# Sheet3.net
KiCad netlist of a schematic drawn in Altium Designer
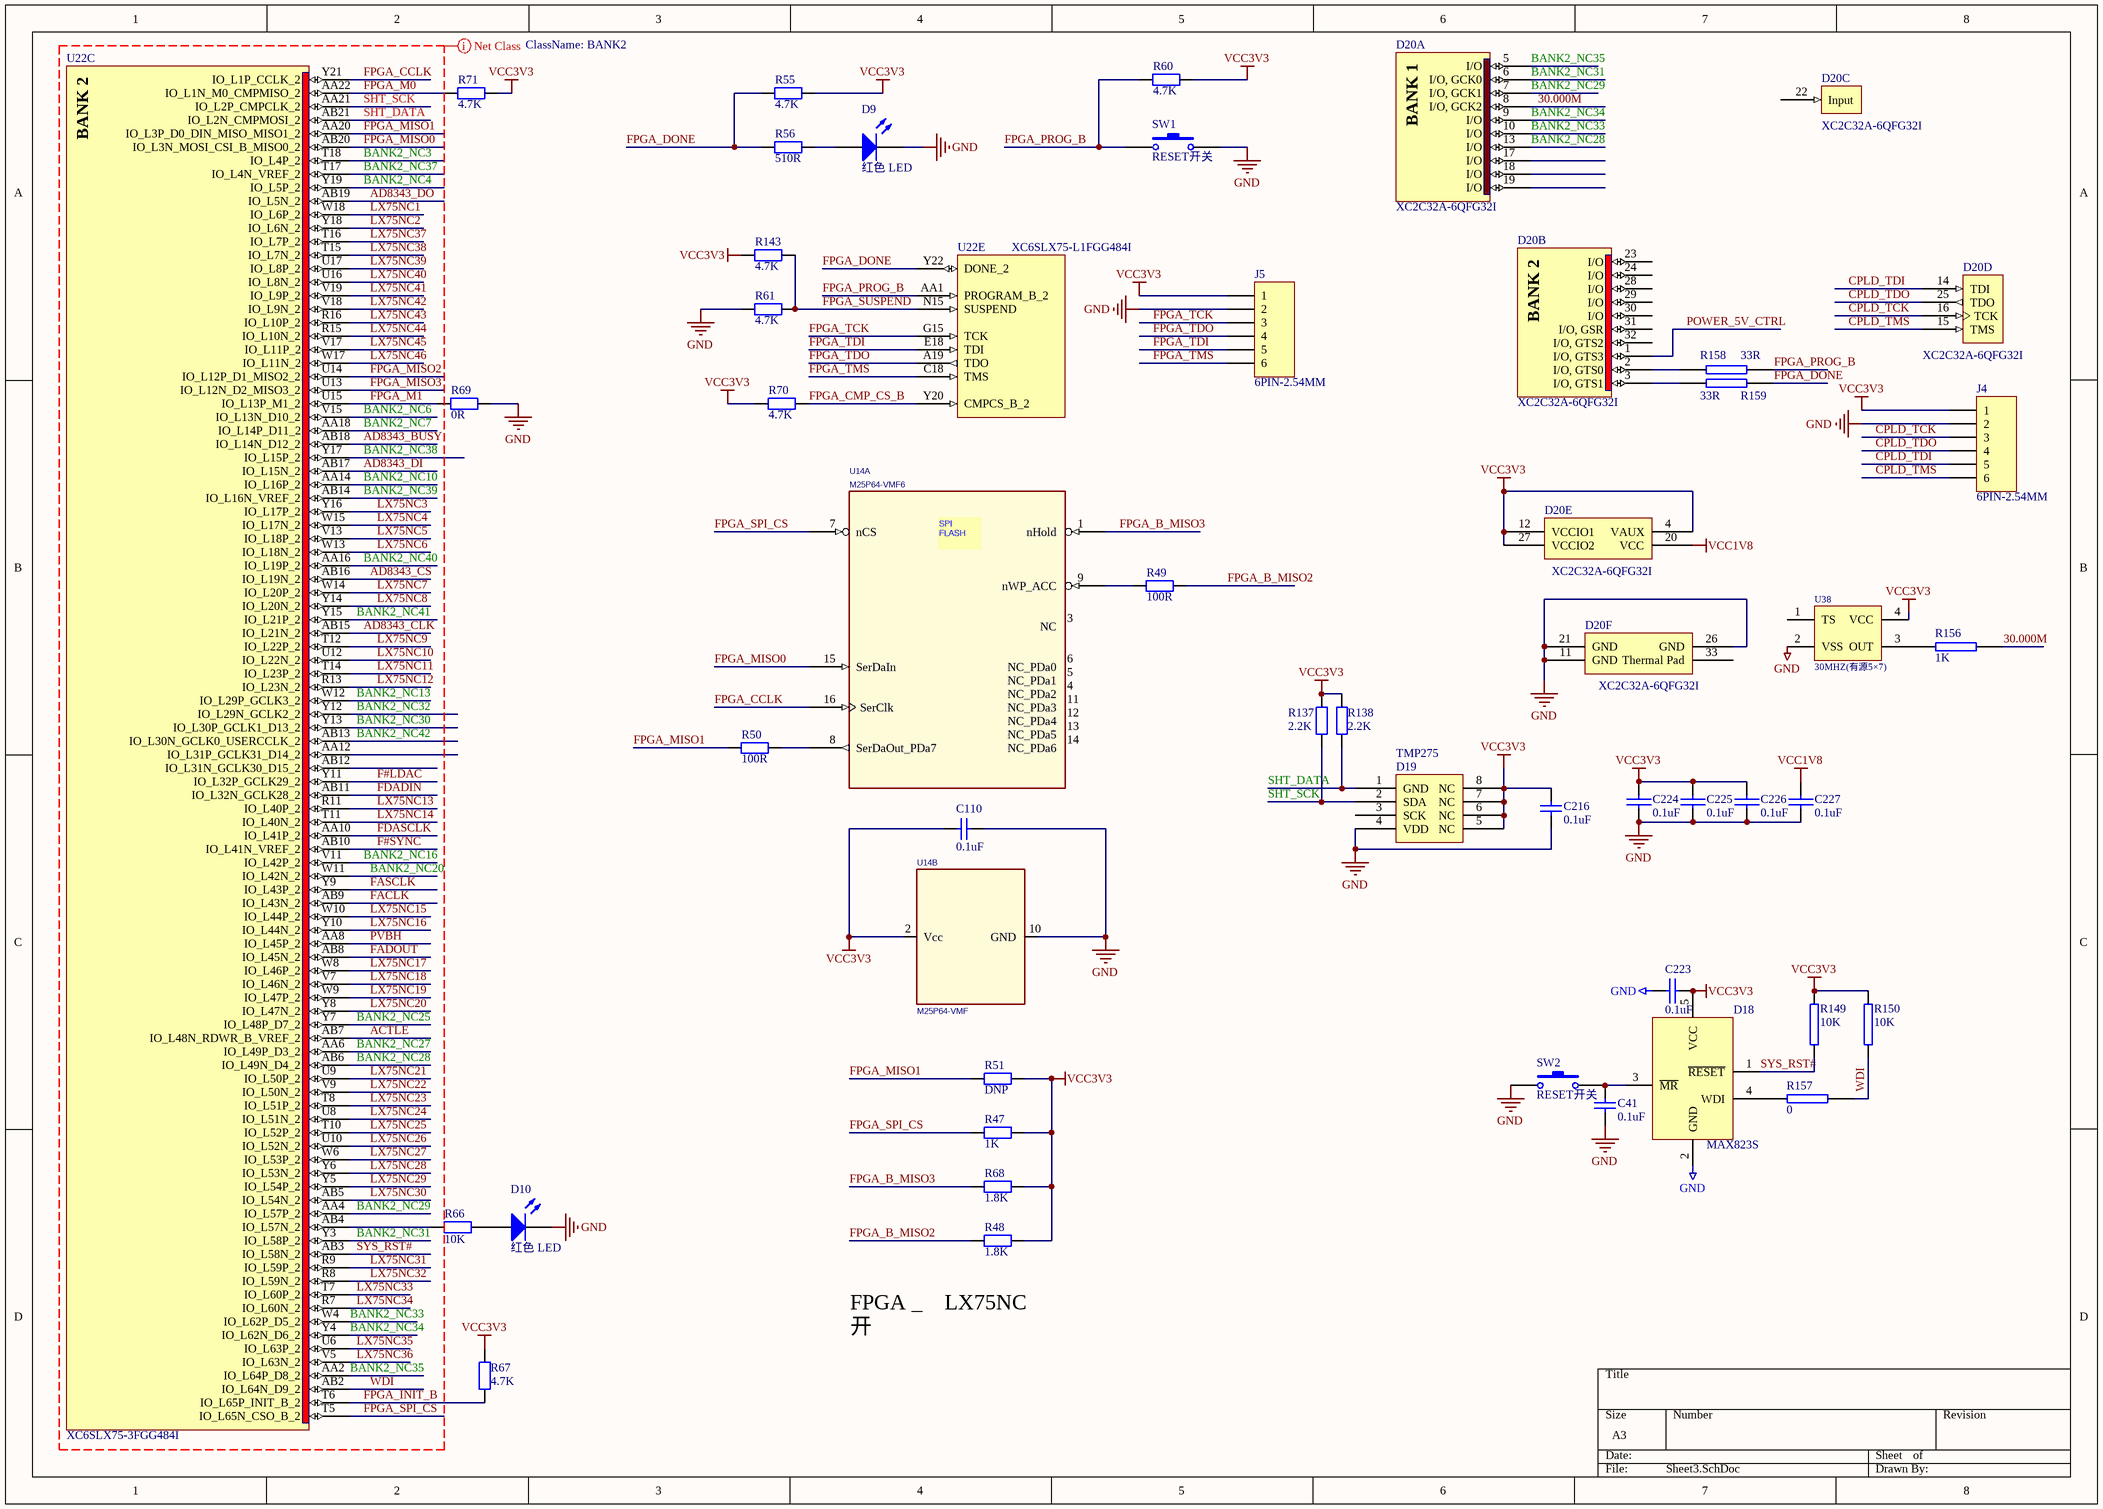
[diagram p0: Sheet3.SchDoc]

(export (version "E")
  (design (tool "Eeschema 10.0.6"))
  (components
    (comp (ref "C41")
      (value "0.1uF")
      (footprint "0603C")
      (description "Capacitor")
      (fields (field (name "PUBLISHER") "Altium Limited"))
      (libsource (lib "Miscellaneous Devices") (part "Cap"))
    )
    (comp (ref "C110")
      (value "0.1uF")
      (footprint "0402C")
      (description "Capacitor")
      (fields (field (name "PUBLISHER") "Altium Limited"))
      (libsource (lib "Miscellaneous Devices") (part "Cap"))
    )
    (comp (ref "C216")
      (value "0.1uF")
      (footprint "0402C")
      (description "Capacitor")
      (fields (field (name "PUBLISHER") "Altium Limited"))
      (libsource (lib "Miscellaneous Devices") (part "Cap"))
    )
    (comp (ref "C223") (value "0.1uF") (footprint "0603X") (libsource (lib "*") (part "2543.S01_104_49")))
    (comp (ref "C224") (value "0.1uF") (footprint "0402C") (libsource (lib "*") (part "2543.S01_104_49")))
    (comp (ref "C225") (value "0.1uF") (footprint "0402C") (libsource (lib "*") (part "2543.S01_104_49")))
    (comp (ref "C226") (value "0.1uF") (footprint "0402C") (libsource (lib "*") (part "2543.S01_104_49")))
    (comp (ref "C227") (value "0.1uF") (footprint "0402C") (libsource (lib "*") (part "2543.S01_104_49")))
    (comp (ref "D9")
      (value "红色 LED")
      (footprint "0805LED")
      (description "Typical RED, GREEN, YELLOW, AMBER GaAs LED")
      (fields (field (name "PUBLISHER") "Altium Limited"))
      (libsource (lib "Miscellaneous Devices") (part "LED2"))
    )
    (comp (ref "D10")
      (value "红色 LED")
      (footprint "0805LED")
      (description "Typical INFRARED GaAs LED")
      (fields (field (name "PUBLISHER") "Altium Limited"))
      (libsource (lib "Miscellaneous Devices") (part "LED0"))
    )
    (comp (ref "D18")
      (value "MAX823S")
      (footprint "MAX823")
      (description "MAX823复位监控芯片")
      (libsource (lib "*") (part "MAX823"))
    )
    (comp (ref "D19") (value "TMP275") (footprint "SMD8XX") (libsource (lib "Schlib1") (part "SHT11")))
    (comp (ref "D20")
      (value "XC2C32A-6QFG32I")
      (footprint "QFG32_N")
      (description "CoolRunner-II 1.8V, 32 Macrocell CPLD, 21 User I/Os, 32-Pin QFNL, Commercial Grade, Pb-Free")
      (fields (field (name "PUBLISHER") "Altium Limited"))
      (libsource (lib "Xilinx CoolRunner II") (part "XC2C32A-6QFG32C"))
    )
    (comp (ref "J4")
      (value "6PIN-2.54MM")
      (footprint "SIP6X")
      (description "Header, 6-Pin")
      (fields (field (name "PUBLISHER") "Altium Limited"))
      (libsource (lib "Miscellaneous Connectors") (part "Header 6"))
    )
    (comp (ref "J5")
      (value "6PIN-2.54MM")
      (footprint "SIP6X")
      (description "Header, 6-Pin")
      (fields (field (name "PUBLISHER") "Altium Limited"))
      (libsource (lib "Miscellaneous Connectors") (part "Header 6"))
    )
    (comp (ref "R47")
      (value "1K")
      (footprint "0603R")
      (description "Resistor")
      (fields (field (name "PUBLISHER") "Altium Limited"))
      (libsource (lib "Miscellaneous Devices") (part "Res2"))
    )
    (comp (ref "R48")
      (value "1.8K")
      (footprint "0603R")
      (description "Resistor")
      (fields (field (name "PUBLISHER") "Altium Limited"))
      (libsource (lib "Miscellaneous Devices") (part "Res2"))
    )
    (comp (ref "R49")
      (value "100R")
      (footprint "0603R")
      (description "Resistor")
      (fields (field (name "PUBLISHER") "Altium Limited"))
      (libsource (lib "Miscellaneous Devices") (part "Res2"))
    )
    (comp (ref "R50")
      (value "100R")
      (footprint "0603R")
      (description "Resistor")
      (fields (field (name "PUBLISHER") "Altium Limited"))
      (libsource (lib "Miscellaneous Devices") (part "Res2"))
    )
    (comp (ref "R51")
      (value "DNP")
      (footprint "0603R")
      (description "Resistor")
      (fields (field (name "PUBLISHER") "Altium Limited"))
      (libsource (lib "Miscellaneous Devices") (part "Res2"))
    )
    (comp (ref "R55")
      (value "4.7K")
      (footprint "0603R")
      (description "Resistor")
      (fields (field (name "PUBLISHER") "Altium Limited"))
      (libsource (lib "Miscellaneous Devices") (part "Res2"))
    )
    (comp (ref "R56")
      (value "510R")
      (footprint "0603R")
      (description "Resistor")
      (fields (field (name "PUBLISHER") "Altium Limited"))
      (libsource (lib "Miscellaneous Devices") (part "Res2"))
    )
    (comp (ref "R60")
      (value "4.7K")
      (footprint "0603R")
      (description "Resistor")
      (fields (field (name "PUBLISHER") "Altium Limited"))
      (libsource (lib "Miscellaneous Devices") (part "Res2"))
    )
    (comp (ref "R61")
      (value "4.7K")
      (footprint "0603R")
      (description "Resistor")
      (fields (field (name "PUBLISHER") "Altium Limited"))
      (libsource (lib "Miscellaneous Devices") (part "Res2"))
    )
    (comp (ref "R66")
      (value "10K")
      (footprint "0603R")
      (description "Resistor")
      (fields (field (name "PUBLISHER") "Altium Limited"))
      (libsource (lib "Miscellaneous Devices") (part "Res2"))
    )
    (comp (ref "R67")
      (value "4.7K")
      (footprint "0603R")
      (description "Resistor")
      (fields (field (name "PUBLISHER") "Altium Limited"))
      (libsource (lib "") (part "Res2_2"))
    )
    (comp (ref "R68")
      (value "1.8K")
      (footprint "0603R")
      (description "Resistor")
      (fields (field (name "PUBLISHER") "Altium Limited"))
      (libsource (lib "Miscellaneous Devices") (part "Res2"))
    )
    (comp (ref "R69")
      (value "0R")
      (footprint "0603R")
      (description "Resistor")
      (fields (field (name "PUBLISHER") "Altium Limited"))
      (libsource (lib "") (part "Res2_1"))
    )
    (comp (ref "R70")
      (value "4.7K")
      (footprint "0603R")
      (description "Resistor")
      (fields (field (name "PUBLISHER") "Altium Limited"))
      (libsource (lib "Miscellaneous Devices") (part "Res2"))
    )
    (comp (ref "R71")
      (value "4.7K")
      (footprint "0603R")
      (description "Resistor")
      (fields (field (name "PUBLISHER") "Altium Limited"))
      (libsource (lib "") (part "Res2_1"))
    )
    (comp (ref "R137")
      (value "2.2K")
      (footprint "0603R")
      (description "Resistor")
      (fields (field (name "PUBLISHER") "Altium Limited"))
      (libsource (lib "") (part "Res2_1"))
    )
    (comp (ref "R138")
      (value "2.2K")
      (footprint "0603R")
      (description "Resistor")
      (fields (field (name "PUBLISHER") "Altium Limited"))
      (libsource (lib "") (part "Res2_1"))
    )
    (comp (ref "R143")
      (value "4.7K")
      (footprint "0603R")
      (description "Resistor")
      (fields (field (name "PUBLISHER") "Altium Limited"))
      (libsource (lib "Miscellaneous Devices") (part "Res2"))
    )
    (comp (ref "R149")
      (value "10K")
      (footprint "0603X")
      (description "电阻")
      (libsource (lib "") (part "RES2_1"))
    )
    (comp (ref "R150")
      (value "10K")
      (footprint "0603X")
      (description "电阻")
      (libsource (lib "") (part "RES2_1"))
    )
    (comp (ref "R156") (value "1K") (footprint "0603") (libsource (lib "*") (part "RES2")))
    (comp (ref "R157") (value "0") (footprint "0603") (libsource (lib "*") (part "RES2")))
    (comp (ref "R158") (value "33R") (footprint "0603R") (libsource (lib "*") (part "RES2")))
    (comp (ref "R159") (value "33R") (footprint "0603R") (libsource (lib "*") (part "RES2")))
    (comp (ref "SW1")
      (value "RESET开关")
      (footprint "RESETKEY")
      (description "Switch")
      (fields (field (name "PUBLISHER") "Altium Limited"))
      (libsource (lib "Miscellaneous Devices") (part "SW-PB"))
    )
    (comp (ref "SW2")
      (value "RESET开关")
      (footprint "RESETKEY")
      (description "Switch")
      (fields (field (name "PUBLISHER") "Altium Limited"))
      (libsource (lib "Miscellaneous Devices") (part "SW-PB"))
    )
    (comp (ref "U14")
      (value "M25P64-VMF")
      (footprint "SOIC16")
      (description "SPI FLASH 128Mbit, 104MHz, 64kB sector")
      (fields (field (name "FULL PART NO") "S25FL128P0XMFI00") (field (name "MANUFACTURER") "Spansion"))
      (libsource (lib "Mpd_Fpga_1") (part "SPI FLASH 128Mb S25FL128P"))
    )
    (comp (ref "U22")
      (value "XC6SLX75-3FGG484I")
      (footprint "FGG484")
      (fields (field (name "PUBLISHER") "Altium Limited"))
      (libsource (lib "Xilinx Spartan-6") (part "XC6SLX45-L1FGG484I"))
    )
    (comp (ref "U38") (value "30MHZ(有源5×7)") (footprint "30M") (libsource (lib "*") (part "CRYSTAL")))
  )
  (nets
    (net (code "1") (name "/30.000M") (class "Default")
      (node (ref "D20") (pin "8") (pinfunction "I/O,_GCK2_8") (pintype "bidirectional"))
      (node (ref "R156") (pin "2") (pinfunction "2_2") (pintype "passive"))
    )
    (net (code "2") (name "/ACTLE") (class "Default")
      (node (ref "U22") (pin "AB7") (pinfunction "IO_L48N_RDWR_B_VREF_2_AB7") (pintype "bidirectional"))
    )
    (net (code "3") (name "/AD8343_BUSY") (class "Default")
      (node (ref "U22") (pin "AB18") (pinfunction "IO_L14N_D12_2_AB18") (pintype "bidirectional"))
    )
    (net (code "4") (name "/AD8343_CLK") (class "Default")
      (node (ref "U22") (pin "AB15") (pinfunction "IO_L21N_2_AB15") (pintype "bidirectional"))
    )
    (net (code "5") (name "/AD8343_CS") (class "Default")
      (node (ref "U22") (pin "AB16") (pinfunction "IO_L19N_2_AB16") (pintype "bidirectional"))
    )
    (net (code "6") (name "/AD8343_DI") (class "Default")
      (node (ref "U22") (pin "AB17") (pinfunction "IO_L15N_2_AB17") (pintype "bidirectional"))
    )
    (net (code "7") (name "/AD8343_DO") (class "Default")
      (node (ref "U22") (pin "AB19") (pinfunction "IO_L5N_2_AB19") (pintype "bidirectional"))
    )
    (net (code "8") (name "/BANK2_NC3") (class "Default")
      (node (ref "U22") (pin "T18") (pinfunction "IO_L4P_2_T18") (pintype "bidirectional"))
    )
    (net (code "9") (name "/BANK2_NC4") (class "Default")
      (node (ref "U22") (pin "Y19") (pinfunction "IO_L5P_2_Y19") (pintype "bidirectional"))
    )
    (net (code "10") (name "/BANK2_NC6") (class "Default")
      (node (ref "U22") (pin "V15") (pinfunction "IO_L13N_D10_2_V15") (pintype "bidirectional"))
    )
    (net (code "11") (name "/BANK2_NC7") (class "Default")
      (node (ref "U22") (pin "AA18") (pinfunction "IO_L14P_D11_2_AA18") (pintype "bidirectional"))
    )
    (net (code "12") (name "/BANK2_NC10") (class "Default")
      (node (ref "U22") (pin "AA14") (pinfunction "IO_L16P_2_AA14") (pintype "bidirectional"))
    )
    (net (code "13") (name "/BANK2_NC13") (class "Default")
      (node (ref "U22") (pin "W12") (pinfunction "IO_L29P_GCLK3_2_W12") (pintype "bidirectional"))
    )
    (net (code "14") (name "/BANK2_NC16") (class "Default")
      (node (ref "U22") (pin "V11") (pinfunction "IO_L42P_2_V11") (pintype "bidirectional"))
    )
    (net (code "15") (name "/BANK2_NC20") (class "Default")
      (node (ref "U22") (pin "W11") (pinfunction "IO_L42N_2_W11") (pintype "bidirectional"))
    )
    (net (code "16") (name "/BANK2_NC25") (class "Default")
      (node (ref "U22") (pin "Y7") (pinfunction "IO_L48P_D7_2_Y7") (pintype "bidirectional"))
    )
    (net (code "17") (name "/BANK2_NC27") (class "Default")
      (node (ref "U22") (pin "AA6") (pinfunction "IO_L49P_D3_2_AA6") (pintype "bidirectional"))
    )
    (net (code "18") (name "/BANK2_NC28") (class "Default")
      (node (ref "D20") (pin "13") (pinfunction "I/O_13") (pintype "bidirectional"))
      (node (ref "U22") (pin "AB6") (pinfunction "IO_L49N_D4_2_AB6") (pintype "bidirectional"))
    )
    (net (code "19") (name "/BANK2_NC29") (class "Default")
      (node (ref "D20") (pin "7") (pinfunction "I/O,_GCK1_7") (pintype "bidirectional"))
      (node (ref "U22") (pin "AA4") (pinfunction "IO_L57P_2_AA4") (pintype "bidirectional"))
    )
    (net (code "20") (name "/BANK2_NC30") (class "Default")
      (node (ref "U22") (pin "Y13") (pinfunction "IO_L30P_GCLK1_D13_2_Y13") (pintype "bidirectional"))
    )
    (net (code "21") (name "/BANK2_NC31") (class "Default")
      (node (ref "D20") (pin "6") (pinfunction "I/O,_GCK0_6") (pintype "bidirectional"))
      (node (ref "U22") (pin "Y3") (pinfunction "IO_L58P_2_Y3") (pintype "bidirectional"))
    )
    (net (code "22") (name "/BANK2_NC32") (class "Default")
      (node (ref "U22") (pin "Y12") (pinfunction "IO_L29N_GCLK2_2_Y12") (pintype "bidirectional"))
    )
    (net (code "23") (name "/BANK2_NC33") (class "Default")
      (node (ref "D20") (pin "10") (pinfunction "I/O_10") (pintype "bidirectional"))
      (node (ref "U22") (pin "W4") (pinfunction "IO_L62P_D5_2_W4") (pintype "bidirectional"))
    )
    (net (code "24") (name "/BANK2_NC34") (class "Default")
      (node (ref "D20") (pin "9") (pinfunction "I/O_9") (pintype "bidirectional"))
      (node (ref "U22") (pin "Y4") (pinfunction "IO_L62N_D6_2_Y4") (pintype "bidirectional"))
    )
    (net (code "25") (name "/BANK2_NC35") (class "Default")
      (node (ref "D20") (pin "5") (pinfunction "I/O_5") (pintype "bidirectional"))
      (node (ref "U22") (pin "AA2") (pinfunction "IO_L64P_D8_2_AA2") (pintype "bidirectional"))
    )
    (net (code "26") (name "/BANK2_NC37") (class "Default")
      (node (ref "U22") (pin "T17") (pinfunction "IO_L4N_VREF_2_T17") (pintype "bidirectional"))
    )
    (net (code "27") (name "/BANK2_NC38") (class "Default")
      (node (ref "U22") (pin "Y17") (pinfunction "IO_L15P_2_Y17") (pintype "bidirectional"))
    )
    (net (code "28") (name "/BANK2_NC39") (class "Default")
      (node (ref "U22") (pin "AB14") (pinfunction "IO_L16N_VREF_2_AB14") (pintype "bidirectional"))
    )
    (net (code "29") (name "/BANK2_NC40") (class "Default")
      (node (ref "U22") (pin "AA16") (pinfunction "IO_L19P_2_AA16") (pintype "bidirectional"))
    )
    (net (code "30") (name "/BANK2_NC41") (class "Default")
      (node (ref "U22") (pin "Y15") (pinfunction "IO_L21P_2_Y15") (pintype "bidirectional"))
    )
    (net (code "31") (name "/BANK2_NC42") (class "Default")
      (node (ref "U22") (pin "AB13") (pinfunction "IO_L30N_GCLK0_USERCCLK_2_AB13") (pintype "bidirectional"))
    )
    (net (code "32") (name "/CPLD_TCK") (class "Default")
      (node (ref "D20") (pin "16") (pinfunction "TCK_16") (pintype "input"))
      (node (ref "J4") (pin "3") (pinfunction "3_3") (pintype "passive"))
    )
    (net (code "33") (name "/CPLD_TDI") (class "Default")
      (node (ref "D20") (pin "14") (pinfunction "TDI_14") (pintype "input"))
      (node (ref "J4") (pin "5") (pinfunction "5_5") (pintype "passive"))
    )
    (net (code "34") (name "/CPLD_TDO") (class "Default")
      (node (ref "D20") (pin "25") (pinfunction "TDO_25") (pintype "output"))
      (node (ref "J4") (pin "4") (pinfunction "4_4") (pintype "passive"))
    )
    (net (code "35") (name "/CPLD_TMS") (class "Default")
      (node (ref "D20") (pin "15") (pinfunction "TMS_15") (pintype "input"))
      (node (ref "J4") (pin "6") (pinfunction "6_6") (pintype "passive"))
    )
    (net (code "36") (name "/F#LDAC") (class "Default")
      (node (ref "U22") (pin "Y11") (pinfunction "IO_L32P_GCLK29_2_Y11") (pintype "bidirectional"))
    )
    (net (code "37") (name "/F#SYNC") (class "Default")
      (node (ref "U22") (pin "AB10") (pinfunction "IO_L41N_VREF_2_AB10") (pintype "bidirectional"))
    )
    (net (code "38") (name "/FACLK") (class "Default")
      (node (ref "U22") (pin "AB9") (pinfunction "IO_L43N_2_AB9") (pintype "bidirectional"))
    )
    (net (code "39") (name "/FADOUT") (class "Default")
      (node (ref "U22") (pin "AB8") (pinfunction "IO_L45N_2_AB8") (pintype "bidirectional"))
    )
    (net (code "40") (name "/FASCLK") (class "Default")
      (node (ref "U22") (pin "Y9") (pinfunction "IO_L43P_2_Y9") (pintype "bidirectional"))
    )
    (net (code "41") (name "/FDADIN") (class "Default")
      (node (ref "U22") (pin "AB11") (pinfunction "IO_L32N_GCLK28_2_AB11") (pintype "bidirectional"))
    )
    (net (code "42") (name "/FDASCLK") (class "Default")
      (node (ref "U22") (pin "AA10") (pinfunction "IO_L41P_2_AA10") (pintype "bidirectional"))
    )
    (net (code "43") (name "/FPGA_B_MISO2") (class "Default")
      (node (ref "R48") (pin "1") (pinfunction "1_1") (pintype "passive"))
      (node (ref "R49") (pin "2") (pinfunction "2_2") (pintype "passive"))
    )
    (net (code "44") (name "/FPGA_B_MISO3") (class "Default")
      (node (ref "R68") (pin "1") (pinfunction "1_1") (pintype "passive"))
      (node (ref "U14") (pin "1") (pinfunction "nHold_1") (pintype "input"))
    )
    (net (code "45") (name "/FPGA_CCLK") (class "Default")
      (node (ref "U14") (pin "16") (pinfunction "SerClk_16") (pintype "input"))
      (node (ref "U22") (pin "Y21") (pinfunction "IO_L1P_CCLK_2_Y21") (pintype "bidirectional"))
    )
    (net (code "46") (name "/FPGA_CMP_CS_B") (class "Default")
      (node (ref "R70") (pin "2") (pinfunction "2_2") (pintype "passive"))
      (node (ref "U22") (pin "Y20") (pinfunction "CMPCS_B_2_Y20") (pintype "input"))
    )
    (net (code "47") (name "/FPGA_DONE") (class "Default")
      (node (ref "R159") (pin "2") (pinfunction "2_2") (pintype "passive"))
      (node (ref "R55") (pin "1") (pinfunction "1_1") (pintype "passive"))
      (node (ref "R56") (pin "1") (pinfunction "1_1") (pintype "passive"))
      (node (ref "U22") (pin "Y22") (pinfunction "DONE_2_Y22") (pintype "bidirectional"))
    )
    (net (code "48") (name "/FPGA_INIT_B") (class "Default")
      (node (ref "R67") (pin "2") (pinfunction "2_2") (pintype "passive"))
      (node (ref "U22") (pin "T6") (pinfunction "IO_L65P_INIT_B_2_T6") (pintype "bidirectional"))
    )
    (net (code "49") (name "/FPGA_M0") (class "Default")
      (node (ref "R71") (pin "2") (pinfunction "2_2") (pintype "passive"))
      (node (ref "U22") (pin "AA22") (pinfunction "IO_L1N_M0_CMPMISO_2_AA22") (pintype "bidirectional"))
    )
    (net (code "50") (name "/FPGA_M1") (class "Default")
      (node (ref "R69") (pin "2") (pinfunction "2_2") (pintype "passive"))
      (node (ref "U22") (pin "U15") (pinfunction "IO_L13P_M1_2_U15") (pintype "bidirectional"))
    )
    (net (code "51") (name "/FPGA_MISO0") (class "Default")
      (node (ref "U14") (pin "15") (pinfunction "SerDaIn_15") (pintype "input"))
      (node (ref "U22") (pin "AB20") (pinfunction "IO_L3N_MOSI_CSI_B_MISO0_2_AB20") (pintype "bidirectional"))
    )
    (net (code "52") (name "/FPGA_MISO1") (class "Default")
      (node (ref "R50") (pin "1") (pinfunction "1_1") (pintype "passive"))
      (node (ref "R51") (pin "1") (pinfunction "1_1") (pintype "passive"))
      (node (ref "U22") (pin "AA20") (pinfunction "IO_L3P_D0_DIN_MISO_MISO1_2_AA20") (pintype "bidirectional"))
    )
    (net (code "53") (name "/FPGA_MISO2") (class "Default")
      (node (ref "U22") (pin "U14") (pinfunction "IO_L12P_D1_MISO2_2_U14") (pintype "bidirectional"))
    )
    (net (code "54") (name "/FPGA_MISO3") (class "Default")
      (node (ref "U22") (pin "U13") (pinfunction "IO_L12N_D2_MISO3_2_U13") (pintype "bidirectional"))
    )
    (net (code "55") (name "/FPGA_PROG_B") (class "Default")
      (node (ref "R158") (pin "2") (pinfunction "2_2") (pintype "passive"))
      (node (ref "R60") (pin "1") (pinfunction "1_1") (pintype "passive"))
      (node (ref "SW1") (pin "1") (pinfunction "1_1") (pintype "passive"))
      (node (ref "U22") (pin "AA1") (pinfunction "PROGRAM_B_2_AA1") (pintype "input"))
    )
    (net (code "56") (name "/FPGA_SPI_CS") (class "Default")
      (node (ref "R47") (pin "1") (pinfunction "1_1") (pintype "passive"))
      (node (ref "U14") (pin "7") (pinfunction "nCS_7") (pintype "input"))
      (node (ref "U22") (pin "T5") (pinfunction "IO_L65N_CSO_B_2_T5") (pintype "bidirectional"))
    )
    (net (code "57") (name "/FPGA_SUSPEND") (class "Default")
      (node (ref "R143") (pin "2") (pinfunction "2_2") (pintype "passive"))
      (node (ref "R61") (pin "2") (pinfunction "2_2") (pintype "passive"))
      (node (ref "U22") (pin "N15") (pinfunction "SUSPEND_N15") (pintype "input"))
    )
    (net (code "58") (name "/FPGA_TCK") (class "Default")
      (node (ref "J5") (pin "3") (pinfunction "3_3") (pintype "passive"))
      (node (ref "U22") (pin "G15") (pinfunction "TCK_G15") (pintype "input"))
    )
    (net (code "59") (name "/FPGA_TDI") (class "Default")
      (node (ref "J5") (pin "5") (pinfunction "5_5") (pintype "passive"))
      (node (ref "U22") (pin "E18") (pinfunction "TDI_E18") (pintype "input"))
    )
    (net (code "60") (name "/FPGA_TDO") (class "Default")
      (node (ref "J5") (pin "4") (pinfunction "4_4") (pintype "passive"))
      (node (ref "U22") (pin "A19") (pinfunction "TDO_A19") (pintype "output"))
    )
    (net (code "61") (name "/FPGA_TMS") (class "Default")
      (node (ref "J5") (pin "6") (pinfunction "6_6") (pintype "passive"))
      (node (ref "U22") (pin "C18") (pinfunction "TMS_C18") (pintype "input"))
    )
    (net (code "62") (name "/LX75NC1") (class "Default")
      (node (ref "U22") (pin "W18") (pinfunction "IO_L6P_2_W18") (pintype "bidirectional"))
    )
    (net (code "63") (name "/LX75NC2") (class "Default")
      (node (ref "U22") (pin "Y18") (pinfunction "IO_L6N_2_Y18") (pintype "bidirectional"))
    )
    (net (code "64") (name "/LX75NC3") (class "Default")
      (node (ref "U22") (pin "Y16") (pinfunction "IO_L17P_2_Y16") (pintype "bidirectional"))
    )
    (net (code "65") (name "/LX75NC4") (class "Default")
      (node (ref "U22") (pin "W15") (pinfunction "IO_L17N_2_W15") (pintype "bidirectional"))
    )
    (net (code "66") (name "/LX75NC5") (class "Default")
      (node (ref "U22") (pin "V13") (pinfunction "IO_L18P_2_V13") (pintype "bidirectional"))
    )
    (net (code "67") (name "/LX75NC6") (class "Default")
      (node (ref "U22") (pin "W13") (pinfunction "IO_L18N_2_W13") (pintype "bidirectional"))
    )
    (net (code "68") (name "/LX75NC7") (class "Default")
      (node (ref "U22") (pin "W14") (pinfunction "IO_L20P_2_W14") (pintype "bidirectional"))
    )
    (net (code "69") (name "/LX75NC8") (class "Default")
      (node (ref "U22") (pin "Y14") (pinfunction "IO_L20N_2_Y14") (pintype "bidirectional"))
    )
    (net (code "70") (name "/LX75NC9") (class "Default")
      (node (ref "U22") (pin "T12") (pinfunction "IO_L22P_2_T12") (pintype "bidirectional"))
    )
    (net (code "71") (name "/LX75NC10") (class "Default")
      (node (ref "U22") (pin "U12") (pinfunction "IO_L22N_2_U12") (pintype "bidirectional"))
    )
    (net (code "72") (name "/LX75NC11") (class "Default")
      (node (ref "U22") (pin "T14") (pinfunction "IO_L23P_2_T14") (pintype "bidirectional"))
    )
    (net (code "73") (name "/LX75NC12") (class "Default")
      (node (ref "U22") (pin "R13") (pinfunction "IO_L23N_2_R13") (pintype "bidirectional"))
    )
    (net (code "74") (name "/LX75NC13") (class "Default")
      (node (ref "U22") (pin "R11") (pinfunction "IO_L40P_2_R11") (pintype "bidirectional"))
    )
    (net (code "75") (name "/LX75NC14") (class "Default")
      (node (ref "U22") (pin "T11") (pinfunction "IO_L40N_2_T11") (pintype "bidirectional"))
    )
    (net (code "76") (name "/LX75NC15") (class "Default")
      (node (ref "U22") (pin "W10") (pinfunction "IO_L44P_2_W10") (pintype "bidirectional"))
    )
    (net (code "77") (name "/LX75NC16") (class "Default")
      (node (ref "U22") (pin "Y10") (pinfunction "IO_L44N_2_Y10") (pintype "bidirectional"))
    )
    (net (code "78") (name "/LX75NC17") (class "Default")
      (node (ref "U22") (pin "W8") (pinfunction "IO_L46P_2_W8") (pintype "bidirectional"))
    )
    (net (code "79") (name "/LX75NC18") (class "Default")
      (node (ref "U22") (pin "V7") (pinfunction "IO_L46N_2_V7") (pintype "bidirectional"))
    )
    (net (code "80") (name "/LX75NC19") (class "Default")
      (node (ref "U22") (pin "W9") (pinfunction "IO_L47P_2_W9") (pintype "bidirectional"))
    )
    (net (code "81") (name "/LX75NC20") (class "Default")
      (node (ref "U22") (pin "Y8") (pinfunction "IO_L47N_2_Y8") (pintype "bidirectional"))
    )
    (net (code "82") (name "/LX75NC21") (class "Default")
      (node (ref "U22") (pin "U9") (pinfunction "IO_L50P_2_U9") (pintype "bidirectional"))
    )
    (net (code "83") (name "/LX75NC22") (class "Default")
      (node (ref "U22") (pin "V9") (pinfunction "IO_L50N_2_V9") (pintype "bidirectional"))
    )
    (net (code "84") (name "/LX75NC23") (class "Default")
      (node (ref "U22") (pin "T8") (pinfunction "IO_L51P_2_T8") (pintype "bidirectional"))
    )
    (net (code "85") (name "/LX75NC24") (class "Default")
      (node (ref "U22") (pin "U8") (pinfunction "IO_L51N_2_U8") (pintype "bidirectional"))
    )
    (net (code "86") (name "/LX75NC25") (class "Default")
      (node (ref "U22") (pin "T10") (pinfunction "IO_L52P_2_T10") (pintype "bidirectional"))
    )
    (net (code "87") (name "/LX75NC26") (class "Default")
      (node (ref "U22") (pin "U10") (pinfunction "IO_L52N_2_U10") (pintype "bidirectional"))
    )
    (net (code "88") (name "/LX75NC27") (class "Default")
      (node (ref "U22") (pin "W6") (pinfunction "IO_L53P_2_W6") (pintype "bidirectional"))
    )
    (net (code "89") (name "/LX75NC28") (class "Default")
      (node (ref "U22") (pin "Y6") (pinfunction "IO_L53N_2_Y6") (pintype "bidirectional"))
    )
    (net (code "90") (name "/LX75NC29") (class "Default")
      (node (ref "U22") (pin "Y5") (pinfunction "IO_L54P_2_Y5") (pintype "bidirectional"))
    )
    (net (code "91") (name "/LX75NC30") (class "Default")
      (node (ref "U22") (pin "AB5") (pinfunction "IO_L54N_2_AB5") (pintype "bidirectional"))
    )
    (net (code "92") (name "/LX75NC31") (class "Default")
      (node (ref "U22") (pin "R9") (pinfunction "IO_L59P_2_R9") (pintype "bidirectional"))
    )
    (net (code "93") (name "/LX75NC32") (class "Default")
      (node (ref "U22") (pin "R8") (pinfunction "IO_L59N_2_R8") (pintype "bidirectional"))
    )
    (net (code "94") (name "/LX75NC33") (class "Default")
      (node (ref "U22") (pin "T7") (pinfunction "IO_L60P_2_T7") (pintype "bidirectional"))
    )
    (net (code "95") (name "/LX75NC34") (class "Default")
      (node (ref "U22") (pin "R7") (pinfunction "IO_L60N_2_R7") (pintype "bidirectional"))
    )
    (net (code "96") (name "/LX75NC35") (class "Default")
      (node (ref "U22") (pin "U6") (pinfunction "IO_L63P_2_U6") (pintype "bidirectional"))
    )
    (net (code "97") (name "/LX75NC36") (class "Default")
      (node (ref "U22") (pin "V5") (pinfunction "IO_L63N_2_V5") (pintype "bidirectional"))
    )
    (net (code "98") (name "/LX75NC37") (class "Default")
      (node (ref "U22") (pin "T16") (pinfunction "IO_L7P_2_T16") (pintype "bidirectional"))
    )
    (net (code "99") (name "/LX75NC38") (class "Default")
      (node (ref "U22") (pin "T15") (pinfunction "IO_L7N_2_T15") (pintype "bidirectional"))
    )
    (net (code "100") (name "/LX75NC39") (class "Default")
      (node (ref "U22") (pin "U17") (pinfunction "IO_L8P_2_U17") (pintype "bidirectional"))
    )
    (net (code "101") (name "/LX75NC40") (class "Default")
      (node (ref "U22") (pin "U16") (pinfunction "IO_L8N_2_U16") (pintype "bidirectional"))
    )
    (net (code "102") (name "/LX75NC41") (class "Default")
      (node (ref "U22") (pin "V19") (pinfunction "IO_L9P_2_V19") (pintype "bidirectional"))
    )
    (net (code "103") (name "/LX75NC42") (class "Default")
      (node (ref "U22") (pin "V18") (pinfunction "IO_L9N_2_V18") (pintype "bidirectional"))
    )
    (net (code "104") (name "/LX75NC43") (class "Default")
      (node (ref "U22") (pin "R16") (pinfunction "IO_L10P_2_R16") (pintype "bidirectional"))
    )
    (net (code "105") (name "/LX75NC44") (class "Default")
      (node (ref "U22") (pin "R15") (pinfunction "IO_L10N_2_R15") (pintype "bidirectional"))
    )
    (net (code "106") (name "/LX75NC45") (class "Default")
      (node (ref "U22") (pin "V17") (pinfunction "IO_L11P_2_V17") (pintype "bidirectional"))
    )
    (net (code "107") (name "/LX75NC46") (class "Default")
      (node (ref "U22") (pin "W17") (pinfunction "IO_L11N_2_W17") (pintype "bidirectional"))
    )
    (net (code "108") (name "/POWER_5V_CTRL") (class "Default")
      (node (ref "D20") (pin "1") (pinfunction "I/O,_GTS3_1") (pintype "bidirectional"))
    )
    (net (code "109") (name "/PVBH") (class "Default")
      (node (ref "U22") (pin "AA8") (pinfunction "IO_L45P_2_AA8") (pintype "bidirectional"))
    )
    (net (code "110") (name "/SHT_DATA") (class "Default")
      (node (ref "D19") (pin "1") (pinfunction "GND_1") (pintype "passive"))
      (node (ref "R138") (pin "2") (pinfunction "2_2") (pintype "passive"))
      (node (ref "U22") (pin "AB21") (pinfunction "IO_L2N_CMPMOSI_2_AB21") (pintype "bidirectional"))
    )
    (net (code "111") (name "/SHT_SCK") (class "Default")
      (node (ref "D19") (pin "2") (pinfunction "SDA_2") (pintype "passive"))
      (node (ref "R137") (pin "2") (pinfunction "2_2") (pintype "passive"))
      (node (ref "U22") (pin "AA21") (pinfunction "IO_L2P_CMPCLK_2_AA21") (pintype "bidirectional"))
    )
    (net (code "112") (name "/SYS_RST#") (class "Default")
      (node (ref "D18") (pin "1") (pinfunction "~{RESET}_1") (pintype "passive"))
      (node (ref "R149") (pin "1") (pinfunction "1_1") (pintype "passive"))
      (node (ref "U22") (pin "AB3") (pinfunction "IO_L58N_2_AB3") (pintype "bidirectional"))
    )
    (net (code "113") (name "/WDI") (class "Default")
      (node (ref "R150") (pin "1") (pinfunction "1_1") (pintype "passive"))
      (node (ref "R157") (pin "2") (pinfunction "2_2") (pintype "passive"))
      (node (ref "U22") (pin "AB2") (pinfunction "IO_L64N_D9_2_AB2") (pintype "bidirectional"))
    )
    (net (code "114") (name "GND") (class "Default")
      (node (ref "C110") (pin "1") (pinfunction "1_1") (pintype "passive"))
      (node (ref "C216") (pin "1") (pinfunction "1_1") (pintype "passive"))
      (node (ref "C223") (pin "1") (pintype "passive"))
      (node (ref "C224") (pin "1") (pintype "passive"))
      (node (ref "C225") (pin "1") (pintype "passive"))
      (node (ref "C226") (pin "1") (pintype "passive"))
      (node (ref "C227") (pin "1") (pintype "passive"))
      (node (ref "C41") (pin "1") (pinfunction "1_1") (pintype "passive"))
      (node (ref "D10") (pin "2") (pinfunction "K_2") (pintype "passive"))
      (node (ref "D18") (pin "2") (pinfunction "GND_2") (pintype "passive"))
      (node (ref "D19") (pin "4") (pinfunction "VDD_4") (pintype "passive"))
      (node (ref "D20") (pin "11") (pinfunction "GND_11") (pintype "power_in"))
      (node (ref "D20") (pin "21") (pinfunction "GND_21") (pintype "power_in"))
      (node (ref "D20") (pin "26") (pinfunction "GND_26") (pintype "power_in"))
      (node (ref "D9") (pin "2") (pinfunction "K_2") (pintype "passive"))
      (node (ref "J4") (pin "2") (pinfunction "2_2") (pintype "passive"))
      (node (ref "J5") (pin "2") (pinfunction "2_2") (pintype "passive"))
      (node (ref "R61") (pin "1") (pinfunction "1_1") (pintype "passive"))
      (node (ref "R69") (pin "1") (pinfunction "1_1") (pintype "passive"))
      (node (ref "SW1") (pin "2") (pinfunction "2_2") (pintype "passive"))
      (node (ref "SW2") (pin "1") (pinfunction "1_1") (pintype "passive"))
      (node (ref "U14") (pin "10") (pinfunction "GND_10") (pintype "power_in"))
      (node (ref "U38") (pin "2") (pinfunction "VSS_2") (pintype "passive"))
    )
    (net (code "115") (name "Net-(D9-A)") (class "Default")
      (node (ref "D9") (pin "1") (pinfunction "A_1") (pintype "passive"))
      (node (ref "R56") (pin "2") (pinfunction "2_2") (pintype "passive"))
    )
    (net (code "116") (name "Net-(D10-A)") (class "Default")
      (node (ref "D10") (pin "1") (pinfunction "A_1") (pintype "passive"))
      (node (ref "R66") (pin "2") (pinfunction "2_2") (pintype "passive"))
    )
    (net (code "117") (name "Net-(D18-WDI)") (class "Default")
      (node (ref "D18") (pin "4") (pinfunction "WDI_4") (pintype "passive"))
      (node (ref "R157") (pin "1") (pinfunction "1_1") (pintype "passive"))
    )
    (net (code "118") (name "Net-(D18-~{MR})") (class "Default")
      (node (ref "C41") (pin "2") (pinfunction "2_2") (pintype "passive"))
      (node (ref "D18") (pin "3") (pinfunction "~{MR}_3") (pintype "passive"))
      (node (ref "SW2") (pin "2") (pinfunction "2_2") (pintype "passive"))
    )
    (net (code "119") (name "Net-(D20B-I{slash}O,_GTS0)") (class "Default")
      (node (ref "D20") (pin "2") (pinfunction "I/O,_GTS0_2") (pintype "bidirectional"))
      (node (ref "R158") (pin "1") (pinfunction "1_1") (pintype "passive"))
    )
    (net (code "120") (name "Net-(D20B-I{slash}O,_GTS1)") (class "Default")
      (node (ref "D20") (pin "3") (pinfunction "I/O,_GTS1_3") (pintype "bidirectional"))
      (node (ref "R159") (pin "1") (pinfunction "1_1") (pintype "passive"))
    )
    (net (code "121") (name "Net-(U14A-SerDaOut_PDa7)") (class "Default")
      (node (ref "R50") (pin "2") (pinfunction "2_2") (pintype "passive"))
      (node (ref "U14") (pin "8") (pinfunction "SerDaOut_PDa7_8") (pintype "output"))
    )
    (net (code "122") (name "Net-(U14A-nWP_ACC)") (class "Default")
      (node (ref "R49") (pin "1") (pinfunction "1_1") (pintype "passive"))
      (node (ref "U14") (pin "9") (pinfunction "nWP_ACC_9") (pintype "input"))
    )
    (net (code "123") (name "Net-(U22C-IO_L57N_2)") (class "Default")
      (node (ref "R66") (pin "1") (pinfunction "1_1") (pintype "passive"))
      (node (ref "U22") (pin "AB4") (pinfunction "IO_L57N_2_AB4") (pintype "bidirectional"))
    )
    (net (code "124") (name "Net-(U38-OUT)") (class "Default")
      (node (ref "R156") (pin "1") (pinfunction "1_1") (pintype "passive"))
      (node (ref "U38") (pin "3") (pinfunction "OUT_3") (pintype "passive"))
    )
    (net (code "125") (name "VCC1V8") (class "Default")
      (node (ref "C227") (pin "2") (pintype "passive"))
      (node (ref "D20") (pin "20") (pinfunction "VCC_20") (pintype "power_in"))
    )
    (net (code "126") (name "VCC3V3") (class "Default")
      (node (ref "C110") (pin "2") (pinfunction "2_2") (pintype "passive"))
      (node (ref "C216") (pin "2") (pinfunction "2_2") (pintype "passive"))
      (node (ref "C223") (pin "2") (pintype "passive"))
      (node (ref "C224") (pin "2") (pintype "passive"))
      (node (ref "C225") (pin "2") (pintype "passive"))
      (node (ref "C226") (pin "2") (pintype "passive"))
      (node (ref "D18") (pin "5") (pinfunction "VCC_5") (pintype "passive"))
      (node (ref "D19") (pin "5") (pinfunction "NC_5") (pintype "passive"))
      (node (ref "D19") (pin "6") (pinfunction "NC_6") (pintype "passive"))
      (node (ref "D19") (pin "7") (pinfunction "NC_7") (pintype "passive"))
      (node (ref "D19") (pin "8") (pinfunction "NC_8") (pintype "passive"))
      (node (ref "D20") (pin "12") (pinfunction "VCCIO1_12") (pintype "power_in"))
      (node (ref "D20") (pin "27") (pinfunction "VCCIO2_27") (pintype "power_in"))
      (node (ref "D20") (pin "4") (pinfunction "VAUX_4") (pintype "power_in"))
      (node (ref "J4") (pin "1") (pinfunction "1_1") (pintype "passive"))
      (node (ref "J5") (pin "1") (pinfunction "1_1") (pintype "passive"))
      (node (ref "R137") (pin "1") (pinfunction "1_1") (pintype "passive"))
      (node (ref "R138") (pin "1") (pinfunction "1_1") (pintype "passive"))
      (node (ref "R143") (pin "1") (pinfunction "1_1") (pintype "passive"))
      (node (ref "R149") (pin "2") (pinfunction "2_2") (pintype "passive"))
      (node (ref "R150") (pin "2") (pinfunction "2_2") (pintype "passive"))
      (node (ref "R47") (pin "2") (pinfunction "2_2") (pintype "passive"))
      (node (ref "R48") (pin "2") (pinfunction "2_2") (pintype "passive"))
      (node (ref "R51") (pin "2") (pinfunction "2_2") (pintype "passive"))
      (node (ref "R55") (pin "2") (pinfunction "2_2") (pintype "passive"))
      (node (ref "R60") (pin "2") (pinfunction "2_2") (pintype "passive"))
      (node (ref "R67") (pin "1") (pinfunction "1_1") (pintype "passive"))
      (node (ref "R68") (pin "2") (pinfunction "2_2") (pintype "passive"))
      (node (ref "R70") (pin "1") (pinfunction "1_1") (pintype "passive"))
      (node (ref "R71") (pin "1") (pinfunction "1_1") (pintype "passive"))
      (node (ref "U14") (pin "2") (pinfunction "Vcc_2") (pintype "power_in"))
      (node (ref "U38") (pin "4") (pinfunction "VCC_4") (pintype "passive"))
    )
    (net (code "127") (name "unconnected-(D19-SCK-Pad3)") (class "Default")
      (node (ref "D19") (pin "3") (pinfunction "SCK_3") (pintype "passive"))
    )
    (net (code "128") (name "unconnected-(D20A-I{slash}O-Pad17)") (class "Default")
      (node (ref "D20") (pin "17") (pinfunction "I/O_17") (pintype "bidirectional"))
    )
    (net (code "129") (name "unconnected-(D20A-I{slash}O-Pad18)") (class "Default")
      (node (ref "D20") (pin "18") (pinfunction "I/O_18") (pintype "bidirectional"))
    )
    (net (code "130") (name "unconnected-(D20A-I{slash}O-Pad19)") (class "Default")
      (node (ref "D20") (pin "19") (pinfunction "I/O_19") (pintype "bidirectional"))
    )
    (net (code "131") (name "unconnected-(D20B-I{slash}O,_GSR-Pad31)") (class "Default")
      (node (ref "D20") (pin "31") (pinfunction "I/O,_GSR_31") (pintype "bidirectional"))
    )
    (net (code "132") (name "unconnected-(D20B-I{slash}O,_GTS2-Pad32)") (class "Default")
      (node (ref "D20") (pin "32") (pinfunction "I/O,_GTS2_32") (pintype "bidirectional"))
    )
    (net (code "133") (name "unconnected-(D20B-I{slash}O-Pad23)") (class "Default")
      (node (ref "D20") (pin "23") (pinfunction "I/O_23") (pintype "bidirectional"))
    )
    (net (code "134") (name "unconnected-(D20B-I{slash}O-Pad24)") (class "Default")
      (node (ref "D20") (pin "24") (pinfunction "I/O_24") (pintype "bidirectional"))
    )
    (net (code "135") (name "unconnected-(D20B-I{slash}O-Pad28)") (class "Default")
      (node (ref "D20") (pin "28") (pinfunction "I/O_28") (pintype "bidirectional"))
    )
    (net (code "136") (name "unconnected-(D20B-I{slash}O-Pad29)") (class "Default")
      (node (ref "D20") (pin "29") (pinfunction "I/O_29") (pintype "bidirectional"))
    )
    (net (code "137") (name "unconnected-(D20B-I{slash}O-Pad30)") (class "Default")
      (node (ref "D20") (pin "30") (pinfunction "I/O_30") (pintype "bidirectional"))
    )
    (net (code "138") (name "unconnected-(D20C-Input-Pad22)") (class "Default")
      (node (ref "D20") (pin "22") (pinfunction "Input_22") (pintype "input"))
    )
    (net (code "139") (name "unconnected-(D20F-Thermal_Pad-Pad33)") (class "Default")
      (node (ref "D20") (pin "33") (pinfunction "Thermal_Pad_33") (pintype "power_in"))
    )
    (net (code "140") (name "unconnected-(U14A-NC-Pad3)") (class "Default")
      (node (ref "U14") (pin "3") (pinfunction "NC_3") (pintype "input"))
    )
    (net (code "141") (name "unconnected-(U14A-NC_PDa0-Pad6)") (class "Default")
      (node (ref "U14") (pin "6") (pinfunction "NC_PDa0_6") (pintype "output"))
    )
    (net (code "142") (name "unconnected-(U14A-NC_PDa1-Pad5)") (class "Default")
      (node (ref "U14") (pin "5") (pinfunction "NC_PDa1_5") (pintype "output"))
    )
    (net (code "143") (name "unconnected-(U14A-NC_PDa2-Pad4)") (class "Default")
      (node (ref "U14") (pin "4") (pinfunction "NC_PDa2_4") (pintype "output"))
    )
    (net (code "144") (name "unconnected-(U14A-NC_PDa3-Pad11)") (class "Default")
      (node (ref "U14") (pin "11") (pinfunction "NC_PDa3_11") (pintype "output"))
    )
    (net (code "145") (name "unconnected-(U14A-NC_PDa4-Pad12)") (class "Default")
      (node (ref "U14") (pin "12") (pinfunction "NC_PDa4_12") (pintype "output"))
    )
    (net (code "146") (name "unconnected-(U14A-NC_PDa5-Pad13)") (class "Default")
      (node (ref "U14") (pin "13") (pinfunction "NC_PDa5_13") (pintype "output"))
    )
    (net (code "147") (name "unconnected-(U14A-NC_PDa6-Pad14)") (class "Default")
      (node (ref "U14") (pin "14") (pinfunction "NC_PDa6_14") (pintype "output"))
    )
    (net (code "148") (name "unconnected-(U22C-IO_L31N_GCLK30_D15_2-PadAB12)") (class "Default")
      (node (ref "U22") (pin "AB12") (pinfunction "IO_L31N_GCLK30_D15_2_AB12") (pintype "bidirectional"))
    )
    (net (code "149") (name "unconnected-(U22C-IO_L31P_GCLK31_D14_2-PadAA12)") (class "Default")
      (node (ref "U22") (pin "AA12") (pinfunction "IO_L31P_GCLK31_D14_2_AA12") (pintype "bidirectional"))
    )
    (net (code "150") (name "unconnected-(U38-TS-Pad1)") (class "Default")
      (node (ref "U38") (pin "1") (pinfunction "TS_1") (pintype "passive"))
    )
  )
)
